# PowerSupply.net
KiCad netlist of a schematic drawn in Altium Designer
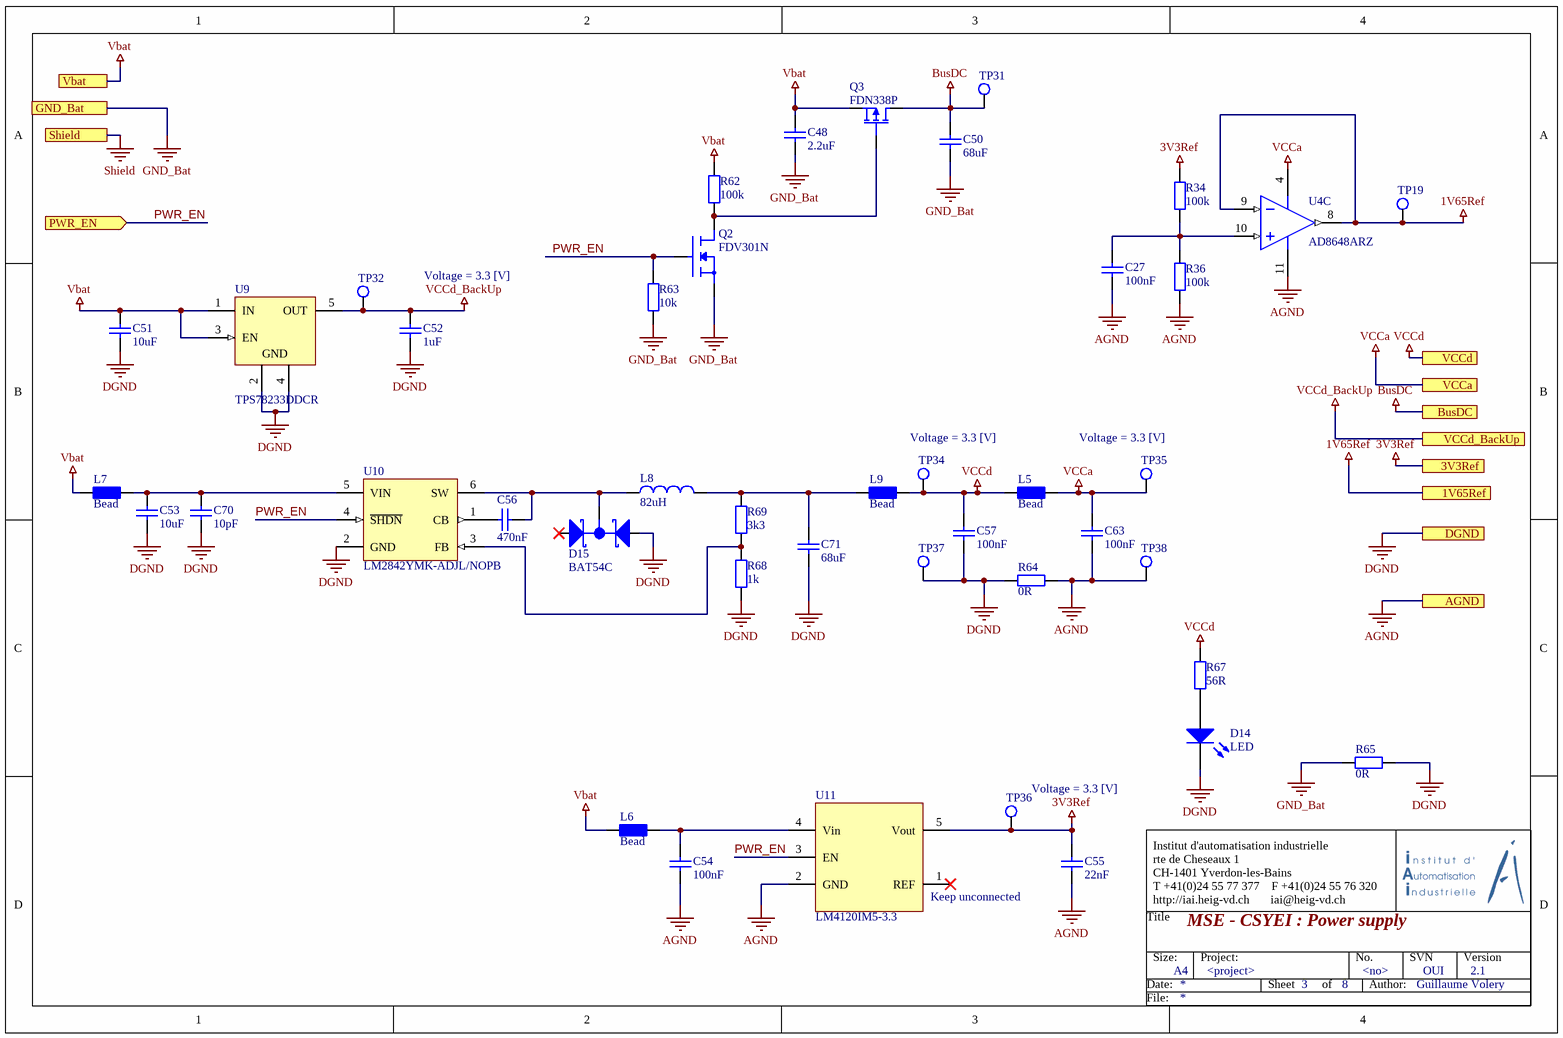
[diagram p0: PowerSupply.SchDoc]

(export (version "E")
  (design (tool "Eeschema 10.0.6"))
  (components
    (comp (ref "C27")
      (value "100nF")
      (footprint "CAPC2012N")
      (description "Capacitor")
      (libsource (lib "Balance") (part "Cap_100nF"))
    )
    (comp (ref "C48")
      (value "2.2uF")
      (footprint "CAPC2012N")
      (description "Capacitor")
      (libsource (lib "Balance") (part "Cap_2.2uF"))
    )
    (comp (ref "C50")
      (value "68uF")
      (footprint "CAP1206")
      (description "Capacitor")
      (libsource (lib "Balance") (part "Cap_68uF"))
    )
    (comp (ref "C51")
      (value "10uF")
      (footprint "CAP1206")
      (description "Capacitor")
      (libsource (lib "Balance") (part "Cap_10uF"))
    )
    (comp (ref "C52")
      (value "1uF")
      (footprint "CAPC2012N")
      (description "Capacitor")
      (libsource (lib "Balance") (part "Cap_1uF"))
    )
    (comp (ref "C53")
      (value "10uF")
      (footprint "CAP1206")
      (description "Capacitor")
      (libsource (lib "Balance") (part "Cap_10uF"))
    )
    (comp (ref "C54")
      (value "100nF")
      (footprint "CAPC2012N")
      (description "Capacitor")
      (libsource (lib "Balance") (part "Cap_100nF"))
    )
    (comp (ref "C55")
      (value "22nF")
      (footprint "CAPC2012N")
      (description "Capacitor")
      (libsource (lib "Balance") (part "Cap_22nF"))
    )
    (comp (ref "C56")
      (value "470nF")
      (footprint "CAPC2012N")
      (description "Capacitor")
      (libsource (lib "Balance") (part "Cap_470nF"))
    )
    (comp (ref "C57")
      (value "100nF")
      (footprint "CAPC2012N")
      (description "Capacitor")
      (libsource (lib "Balance") (part "Cap_100nF"))
    )
    (comp (ref "C63")
      (value "100nF")
      (footprint "CAPC2012N")
      (description "Capacitor")
      (libsource (lib "Balance") (part "Cap_100nF"))
    )
    (comp (ref "C70")
      (value "10pF")
      (footprint "CAPC2012N")
      (description "Capacitor")
      (libsource (lib "Balance") (part "Cap_10pF"))
    )
    (comp (ref "C71")
      (value "68uF")
      (footprint "CAP1206")
      (description "Capacitor")
      (libsource (lib "Balance") (part "Cap_68uF"))
    )
    (comp (ref "D14")
      (value "LED")
      (footprint "LED2012N")
      (libsource (lib "Balance") (part "LED_Green_0805"))
    )
    (comp (ref "D15") (value "BAT54C") (footprint "SOT23-3N") (libsource (lib "Balance") (part "BAT54C")))
    (comp (ref "L5") (value "Bead") (footprint "RESC2012N") (libsource (lib "Balance") (part "Bead")))
    (comp (ref "L6") (value "Bead") (footprint "RESC2012N") (libsource (lib "Balance") (part "Bead")))
    (comp (ref "L7") (value "Bead") (footprint "RESC2012N") (libsource (lib "Balance") (part "Bead")))
    (comp (ref "L8")
      (value "82uH")
      (footprint "SRR1260A-820MC")
      (libsource (lib "Balance") (part "SRR1260A-820M"))
    )
    (comp (ref "L9") (value "Bead") (footprint "RESC2012N") (libsource (lib "Balance") (part "Bead")))
    (comp (ref "Q2") (value "FDV301N") (footprint "SOT23-3N") (libsource (lib "Balance") (part "FDV301N")))
    (comp (ref "Q3")
      (value "FDN338P")
      (footprint "SOT23-3N")
      (description "MOSFet P")
      (libsource (lib "Balance") (part "FDN338P"))
    )
    (comp (ref "R34")
      (value "100k")
      (footprint "RESC2012N")
      (description "Resistor")
      (libsource (lib "Balance") (part "Res_100k"))
    )
    (comp (ref "R36")
      (value "100k")
      (footprint "RESC2012N")
      (description "Resistor")
      (libsource (lib "Balance") (part "Res_100k"))
    )
    (comp (ref "R62")
      (value "100k")
      (footprint "RESC2012N")
      (description "Resistor")
      (libsource (lib "") (part "Res_100k_1"))
    )
    (comp (ref "R63")
      (value "10k")
      (footprint "RESC2012N")
      (description "Resistor")
      (libsource (lib "Balance") (part "Res_10k"))
    )
    (comp (ref "R64")
      (value "0R")
      (footprint "RESC2012N")
      (description "Resistor")
      (libsource (lib "Balance") (part "Res_0R"))
    )
    (comp (ref "R65")
      (value "0R")
      (footprint "RESC2012N")
      (description "Resistor")
      (libsource (lib "Balance") (part "Res_0R"))
    )
    (comp (ref "R67")
      (value "56R")
      (footprint "RESC2012N")
      (description "Resistor")
      (libsource (lib "Balance") (part "Res_56R"))
    )
    (comp (ref "R68")
      (value "1k")
      (footprint "RESC2012N")
      (description "Resistor")
      (libsource (lib "Balance") (part "Res_1k"))
    )
    (comp (ref "R69")
      (value "3k3")
      (footprint "RESC2012N")
      (description "Resistor")
      (libsource (lib "Balance") (part "Res_3k3"))
    )
    (comp (ref "TP19")
      (value "TP")
      (footprint "Testpoint")
      (description "=Value")
      (libsource (lib "Balance") (part "TP"))
    )
    (comp (ref "TP31")
      (value "TP")
      (footprint "Testpoint")
      (description "=Value")
      (libsource (lib "Balance") (part "TP"))
    )
    (comp (ref "TP32")
      (value "TP")
      (footprint "Testpoint")
      (description "=Value")
      (libsource (lib "Balance") (part "TP"))
    )
    (comp (ref "TP34")
      (value "TP")
      (footprint "Testpoint")
      (description "=Value")
      (libsource (lib "Balance") (part "TP"))
    )
    (comp (ref "TP35")
      (value "TP")
      (footprint "Testpoint")
      (description "=Value")
      (libsource (lib "Balance") (part "TP"))
    )
    (comp (ref "TP36")
      (value "TP")
      (footprint "Testpoint")
      (description "=Value")
      (libsource (lib "Balance") (part "TP"))
    )
    (comp (ref "TP37")
      (value "TP")
      (footprint "Testpoint")
      (description "=Value")
      (libsource (lib "Balance") (part "TP"))
    )
    (comp (ref "TP38")
      (value "TP")
      (footprint "Testpoint")
      (description "=Value")
      (libsource (lib "Balance") (part "TP"))
    )
    (comp (ref "U4")
      (value "AD8648ARZ")
      (footprint "ADI-R-14_M")
      (fields (field (name "GENERIC PART NUMBER") "AD8648") (field (name "MANUFACTURER") "Analog Devices"))
      (libsource (lib "Balance") (part "AD8648ARZ"))
    )
    (comp (ref "U9")
      (value "TPS78233DDCR")
      (footprint "SOT-23-5")
      (fields (field (name "MANUFACTURER") "Texas Instruments"))
      (libsource (lib "Balance") (part "TPS78233DDCR"))
    )
    (comp (ref "U10")
      (value "LM2842YMK-ADJL/NOPB")
      (footprint "SOT-23-6")
      (description "600 mA up to 42V Input Step-Down DC/DC Regulator, Thin 6-pin SOT23, Pb-Free, 1000 Reel")
      (libsource (lib "Balance") (part "LM2842YMK-ADJL/NOPB"))
    )
    (comp (ref "U11")
      (value "LM4120IM5-3.3")
      (footprint "SOT-23-5")
      (libsource (lib "Balance") (part "LM4120IM5-3.3"))
    )
  )
  (nets
    (net (code "1") (name "/PWR_EN") (class "Default")
      (node (ref "Q2") (pin "1") (pinfunction "G_1") (pintype "passive"))
      (node (ref "R63") (pin "2") (pinfunction "2_2") (pintype "passive"))
      (node (ref "U10") (pin "4") (pinfunction "~{SHDN}_4") (pintype "input"))
      (node (ref "U11") (pin "3") (pinfunction "EN_3") (pintype "passive"))
    )
    (net (code "2") (name "1V65Ref") (class "Default")
      (node (ref "TP19") (pin "1") (pinfunction "1_1") (pintype "passive"))
      (node (ref "U4") (pin "8") (pinfunction "OUT_C_8") (pintype "output"))
      (node (ref "U4") (pin "9") (pinfunction "-IN_C_9") (pintype "input"))
    )
    (net (code "3") (name "3V3Ref") (class "Default")
      (node (ref "C55") (pin "2") (pinfunction "2_2") (pintype "passive"))
      (node (ref "R34") (pin "2") (pinfunction "2_2") (pintype "passive"))
      (node (ref "TP36") (pin "1") (pinfunction "1_1") (pintype "passive"))
      (node (ref "U11") (pin "5") (pinfunction "Vout_5") (pintype "power_in"))
    )
    (net (code "4") (name "AGND") (class "Default")
      (node (ref "C27") (pin "1") (pinfunction "1_1") (pintype "passive"))
      (node (ref "C54") (pin "1") (pinfunction "1_1") (pintype "passive"))
      (node (ref "C55") (pin "1") (pinfunction "1_1") (pintype "passive"))
      (node (ref "C63") (pin "1") (pinfunction "1_1") (pintype "passive"))
      (node (ref "R36") (pin "1") (pinfunction "1_1") (pintype "passive"))
      (node (ref "R64") (pin "2") (pinfunction "2_2") (pintype "passive"))
      (node (ref "TP38") (pin "1") (pinfunction "1_1") (pintype "passive"))
      (node (ref "U11") (pin "2") (pinfunction "GND_2") (pintype "power_in"))
      (node (ref "U4") (pin "11") (pinfunction "-V_11") (pintype "power_in"))
    )
    (net (code "5") (name "BusDC") (class "Default")
      (node (ref "C50") (pin "2") (pinfunction "2_2") (pintype "passive"))
      (node (ref "Q3") (pin "3") (pinfunction "D_3") (pintype "passive"))
      (node (ref "TP31") (pin "1") (pinfunction "1_1") (pintype "passive"))
    )
    (net (code "6") (name "DGND") (class "Default")
      (node (ref "C51") (pin "1") (pinfunction "1_1") (pintype "passive"))
      (node (ref "C52") (pin "1") (pinfunction "1_1") (pintype "passive"))
      (node (ref "C53") (pin "1") (pinfunction "1_1") (pintype "passive"))
      (node (ref "C57") (pin "1") (pinfunction "1_1") (pintype "passive"))
      (node (ref "C70") (pin "1") (pinfunction "1_1") (pintype "passive"))
      (node (ref "C71") (pin "1") (pinfunction "1_1") (pintype "passive"))
      (node (ref "D14") (pin "2") (pinfunction "K_2") (pintype "passive"))
      (node (ref "D15") (pin "2") (pinfunction "A2_2") (pintype "passive"))
      (node (ref "R64") (pin "1") (pinfunction "1_1") (pintype "passive"))
      (node (ref "R65") (pin "2") (pinfunction "2_2") (pintype "passive"))
      (node (ref "R68") (pin "2") (pinfunction "2_2") (pintype "passive"))
      (node (ref "TP37") (pin "1") (pinfunction "1_1") (pintype "passive"))
      (node (ref "U10") (pin "2") (pinfunction "GND_2") (pintype "power_in"))
      (node (ref "U9") (pin "2") (pinfunction "GND_2") (pintype "passive"))
      (node (ref "U9") (pin "4") (pinfunction "GND_4") (pintype "passive"))
    )
    (net (code "7") (name "GND_Bat") (class "Default")
      (node (ref "C48") (pin "1") (pinfunction "1_1") (pintype "passive"))
      (node (ref "C50") (pin "1") (pinfunction "1_1") (pintype "passive"))
      (node (ref "Q2") (pin "2") (pinfunction "S_2") (pintype "passive"))
      (node (ref "R63") (pin "1") (pinfunction "1_1") (pintype "passive"))
      (node (ref "R65") (pin "1") (pinfunction "1_1") (pintype "passive"))
    )
    (net (code "8") (name "Net-(C71-Pad2)") (class "Default")
      (node (ref "C71") (pin "2") (pinfunction "2_2") (pintype "passive"))
      (node (ref "L8") (pin "2") (pinfunction "2_2") (pintype "passive"))
      (node (ref "L9") (pin "1") (pinfunction "1_1") (pintype "passive"))
      (node (ref "R69") (pin "2") (pinfunction "2_2") (pintype "passive"))
    )
    (net (code "9") (name "Net-(D14-A)") (class "Default")
      (node (ref "D14") (pin "1") (pinfunction "A_1") (pintype "passive"))
      (node (ref "R67") (pin "1") (pinfunction "1_1") (pintype "passive"))
    )
    (net (code "10") (name "Net-(D15-K)") (class "Default")
      (node (ref "C56") (pin "2") (pinfunction "2_2") (pintype "passive"))
      (node (ref "D15") (pin "3") (pinfunction "K_3") (pintype "passive"))
      (node (ref "L8") (pin "1") (pinfunction "1_1") (pintype "passive"))
      (node (ref "U10") (pin "6") (pinfunction "SW_6") (pintype "power_in"))
    )
    (net (code "11") (name "Net-(Q2-D)") (class "Default")
      (node (ref "Q2") (pin "3") (pinfunction "D_3") (pintype "passive"))
      (node (ref "Q3") (pin "1") (pinfunction "G_1") (pintype "passive"))
      (node (ref "R62") (pin "1") (pinfunction "1_1") (pintype "passive"))
    )
    (net (code "12") (name "Net-(U4C-+IN_C)") (class "Default")
      (node (ref "C27") (pin "2") (pinfunction "2_2") (pintype "passive"))
      (node (ref "R34") (pin "1") (pinfunction "1_1") (pintype "passive"))
      (node (ref "R36") (pin "2") (pinfunction "2_2") (pintype "passive"))
      (node (ref "U4") (pin "10") (pinfunction "+IN_C_10") (pintype "input"))
    )
    (net (code "13") (name "Net-(U10-CB)") (class "Default")
      (node (ref "C56") (pin "1") (pinfunction "1_1") (pintype "passive"))
      (node (ref "U10") (pin "1") (pinfunction "CB_1") (pintype "output"))
    )
    (net (code "14") (name "Net-(U10-FB)") (class "Default")
      (node (ref "R68") (pin "1") (pinfunction "1_1") (pintype "passive"))
      (node (ref "R69") (pin "1") (pinfunction "1_1") (pintype "passive"))
      (node (ref "U10") (pin "3") (pinfunction "FB_3") (pintype "input"))
    )
    (net (code "15") (name "Net-(U10-VIN)") (class "Default")
      (node (ref "C53") (pin "2") (pinfunction "2_2") (pintype "passive"))
      (node (ref "C70") (pin "2") (pinfunction "2_2") (pintype "passive"))
      (node (ref "L7") (pin "2") (pinfunction "2_2") (pintype "passive"))
      (node (ref "U10") (pin "5") (pinfunction "VIN_5") (pintype "power_in"))
    )
    (net (code "16") (name "Net-(U11-Vin)") (class "Default")
      (node (ref "C54") (pin "2") (pinfunction "2_2") (pintype "passive"))
      (node (ref "L6") (pin "2") (pinfunction "2_2") (pintype "passive"))
      (node (ref "U11") (pin "4") (pinfunction "Vin_4") (pintype "power_in"))
    )
    (net (code "18") (name "VCCa") (class "Default")
      (node (ref "C63") (pin "2") (pinfunction "2_2") (pintype "passive"))
      (node (ref "L5") (pin "2") (pinfunction "2_2") (pintype "passive"))
      (node (ref "TP35") (pin "1") (pinfunction "1_1") (pintype "passive"))
      (node (ref "U4") (pin "4") (pinfunction "+V_4") (pintype "power_in"))
    )
    (net (code "19") (name "VCCd") (class "Default")
      (node (ref "C57") (pin "2") (pinfunction "2_2") (pintype "passive"))
      (node (ref "L5") (pin "1") (pinfunction "1_1") (pintype "passive"))
      (node (ref "L9") (pin "2") (pinfunction "2_2") (pintype "passive"))
      (node (ref "R67") (pin "2") (pinfunction "2_2") (pintype "passive"))
      (node (ref "TP34") (pin "1") (pinfunction "1_1") (pintype "passive"))
    )
    (net (code "20") (name "VCCd_BackUp") (class "Default")
      (node (ref "C52") (pin "2") (pinfunction "2_2") (pintype "passive"))
      (node (ref "TP32") (pin "1") (pinfunction "1_1") (pintype "passive"))
      (node (ref "U9") (pin "5") (pinfunction "OUT_5") (pintype "power_in"))
    )
    (net (code "21") (name "Vbat") (class "Default")
      (node (ref "C48") (pin "2") (pinfunction "2_2") (pintype "passive"))
      (node (ref "C51") (pin "2") (pinfunction "2_2") (pintype "passive"))
      (node (ref "L6") (pin "1") (pinfunction "1_1") (pintype "passive"))
      (node (ref "L7") (pin "1") (pinfunction "1_1") (pintype "passive"))
      (node (ref "Q3") (pin "2") (pinfunction "S_2") (pintype "passive"))
      (node (ref "R62") (pin "2") (pinfunction "2_2") (pintype "passive"))
      (node (ref "U9") (pin "1") (pinfunction "IN_1") (pintype "power_in"))
      (node (ref "U9") (pin "3") (pinfunction "EN_3") (pintype "input"))
    )
    (net (code "22") (name "unconnected-(D15-A1-Pad1)") (class "Default")
      (node (ref "D15") (pin "1") (pinfunction "A1_1") (pintype "passive+no_connect"))
    )
    (net (code "23") (name "unconnected-(U11-REF-Pad1)") (class "Default")
      (node (ref "U11") (pin "1") (pinfunction "REF_1") (pintype "power_in+no_connect"))
    )
  )
)
